# single_esc.net
KiCad netlist of a schematic drawn in Altium Designer
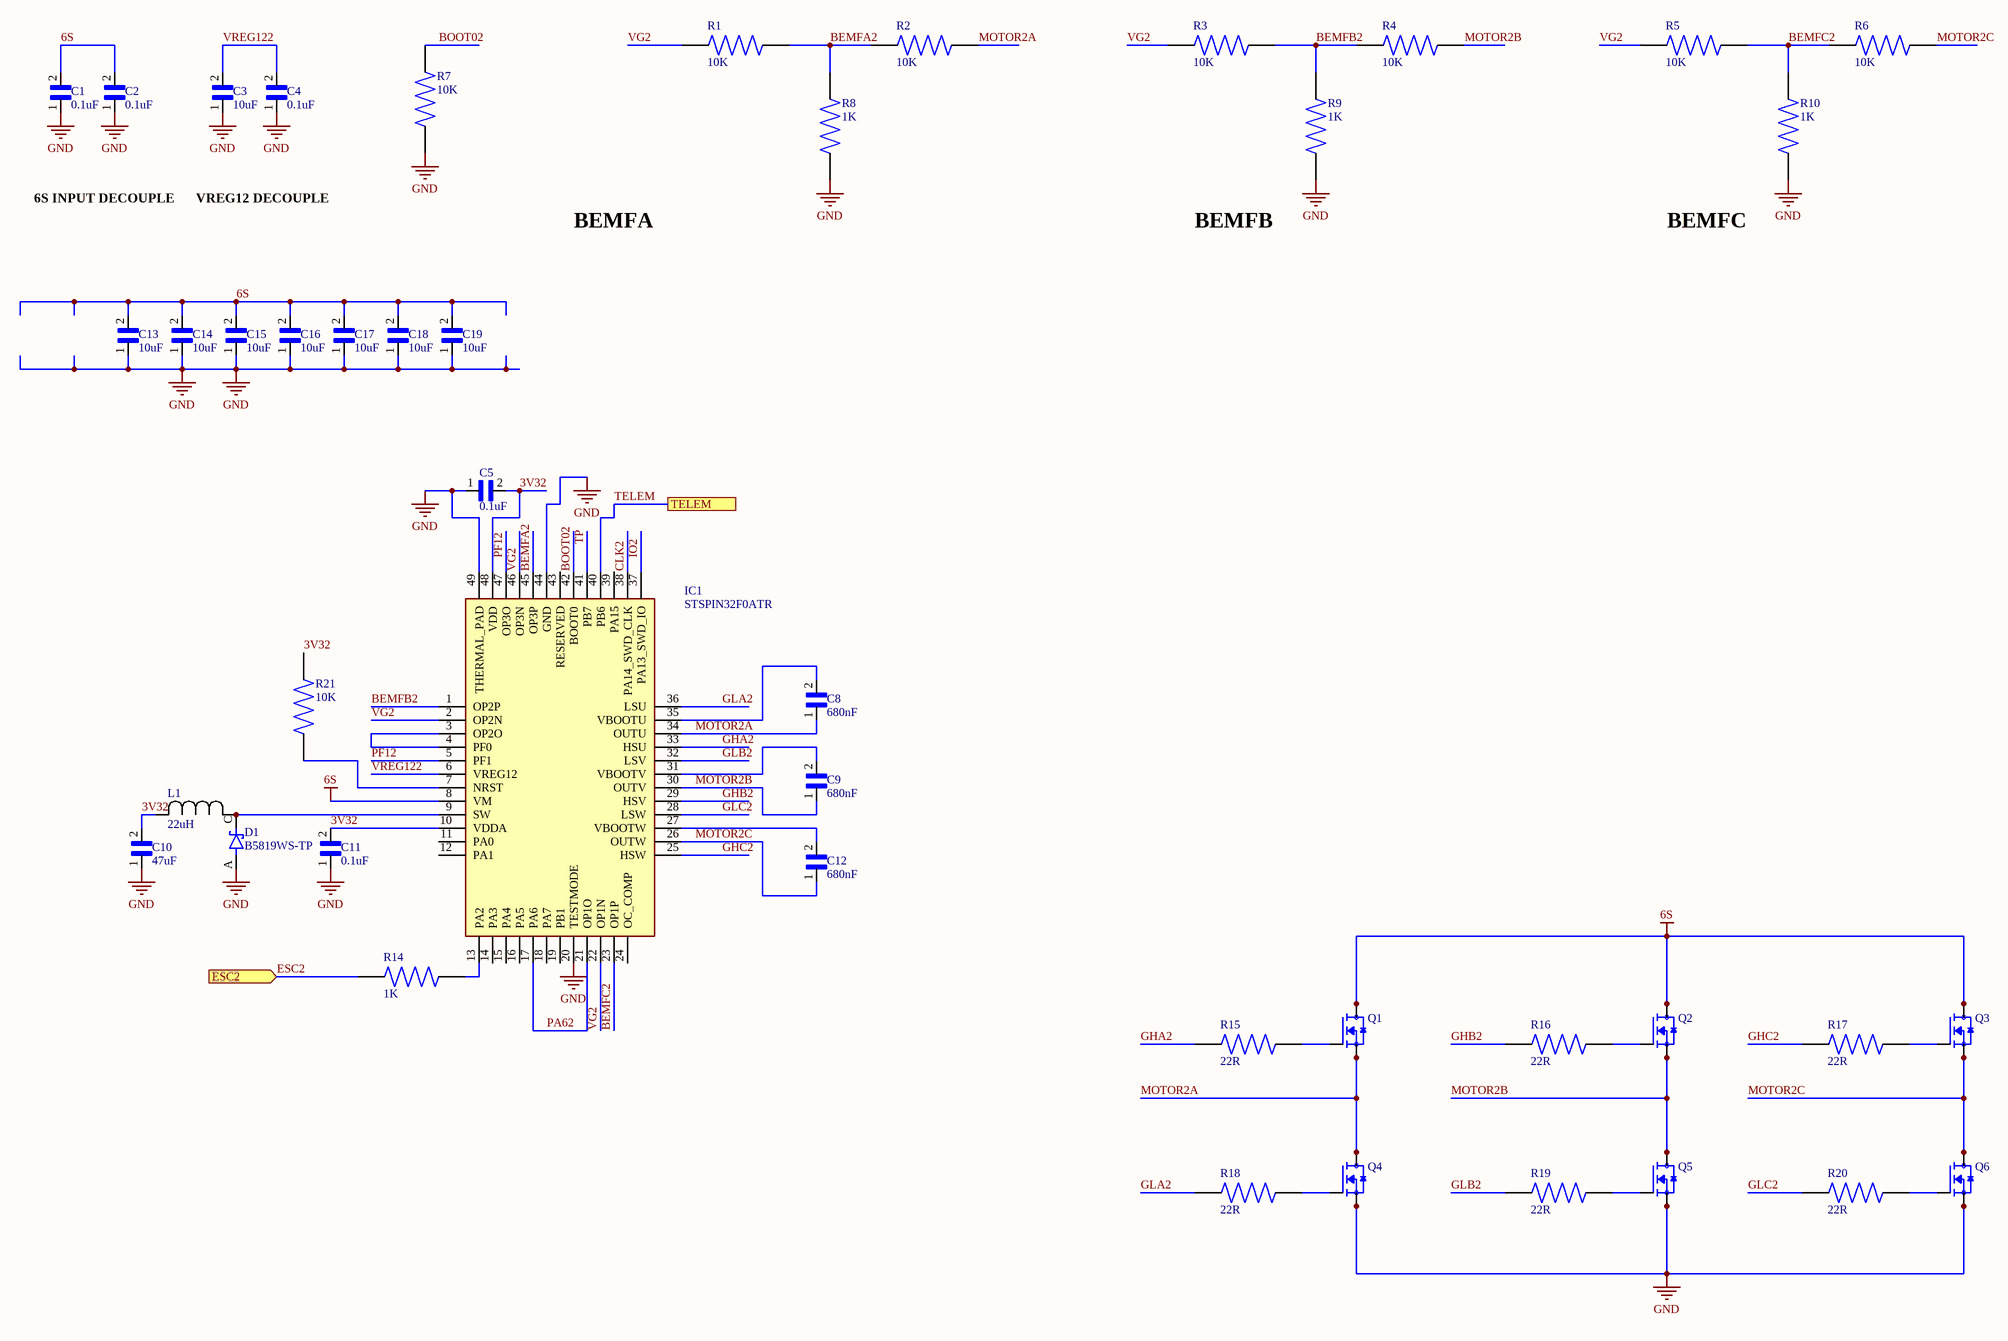
[diagram p0: single esc.SchDoc]

(export (version "E")
  (design (tool "Eeschema 10.0.6"))
  (components
    (comp (ref "C1")
      (value "0.1uF")
      (footprint "CAPC1005X55N")
      (fields (field (name "MP") "GRM1555C1H222JA01D"))
      (libsource (lib "GRM1555C1H222JA01D") (part "GRM1555C1H222JA01D"))
    )
    (comp (ref "C2")
      (value "0.1uF")
      (footprint "CAPC1005X55N")
      (fields (field (name "MP") "GRM1555C1H222JA01D"))
      (libsource (lib "GRM1555C1H222JA01D") (part "GRM1555C1H222JA01D"))
    )
    (comp (ref "C3")
      (value "10uF")
      (footprint "CAPC1608X90N")
      (description "SMD Capacitor X7R(EIA) with Capacitance: 0.22uF Tol. 5%. Rated Voltage: 25Vdc")
      (fields (field (name "MP") "GRM188R71E224JA88D"))
      (libsource (lib "GRM188R71E224JA88D") (part "GRM188R71E224JA88D"))
    )
    (comp (ref "C4")
      (value "0.1uF")
      (footprint "CAPC1005X55N")
      (fields (field (name "MP") "GRM1555C1H222JA01D"))
      (libsource (lib "GRM1555C1H222JA01D") (part "GRM1555C1H222JA01D"))
    )
    (comp (ref "C5")
      (value "0.1uF")
      (footprint "CAPC1005X55N")
      (fields (field (name "MP") "GRM1555C1H222JA01D"))
      (libsource (lib "") (part "GRM1555C1H222JA01D_1"))
    )
    (comp (ref "C8")
      (value "680nF")
      (footprint "CAPC1005X55N")
      (fields (field (name "MP") "GRM1555C1H222JA01D"))
      (libsource (lib "GRM1555C1H222JA01D") (part "GRM1555C1H222JA01D"))
    )
    (comp (ref "C9")
      (value "680nF")
      (footprint "CAPC1005X55N")
      (fields (field (name "MP") "GRM1555C1H222JA01D"))
      (libsource (lib "GRM1555C1H222JA01D") (part "GRM1555C1H222JA01D"))
    )
    (comp (ref "C10")
      (value "47uF")
      (footprint "CAPC1608X90N")
      (description "SMD Capacitor X7R(EIA) with Capacitance: 0.22uF Tol. 5%. Rated Voltage: 25Vdc")
      (fields (field (name "MP") "GRM188R71E224JA88D"))
      (libsource (lib "GRM188R71E224JA88D") (part "GRM188R71E224JA88D"))
    )
    (comp (ref "C11")
      (value "0.1uF")
      (footprint "CAPC1005X55N")
      (fields (field (name "MP") "GRM1555C1H222JA01D"))
      (libsource (lib "GRM1555C1H222JA01D") (part "GRM1555C1H222JA01D"))
    )
    (comp (ref "C12")
      (value "680nF")
      (footprint "CAPC1005X55N")
      (fields (field (name "MP") "GRM1555C1H222JA01D"))
      (libsource (lib "GRM1555C1H222JA01D") (part "GRM1555C1H222JA01D"))
    )
    (comp (ref "C13")
      (value "10uF")
      (footprint "CAPC3216X190N")
      (description "Ceramic Capacitor")
      (fields (field (name "MP") "GRM31CC80G227ME11K"))
      (libsource (lib "GRM31CC80G227ME11K") (part "GRM31CC80G227ME11K"))
    )
    (comp (ref "C14")
      (value "10uF")
      (footprint "CAPC3216X190N")
      (description "Ceramic Capacitor")
      (fields (field (name "MP") "GRM31CC80G227ME11K"))
      (libsource (lib "GRM31CC80G227ME11K") (part "GRM31CC80G227ME11K"))
    )
    (comp (ref "C15")
      (value "10uF")
      (footprint "CAPC3216X190N")
      (description "Ceramic Capacitor")
      (fields (field (name "MP") "GRM31CC80G227ME11K"))
      (libsource (lib "GRM31CC80G227ME11K") (part "GRM31CC80G227ME11K"))
    )
    (comp (ref "C16")
      (value "10uF")
      (footprint "CAPC3216X190N")
      (description "Ceramic Capacitor")
      (fields (field (name "MP") "GRM31CC80G227ME11K"))
      (libsource (lib "GRM31CC80G227ME11K") (part "GRM31CC80G227ME11K"))
    )
    (comp (ref "C17")
      (value "10uF")
      (footprint "CAPC3216X190N")
      (description "Ceramic Capacitor")
      (fields (field (name "MP") "GRM31CC80G227ME11K"))
      (libsource (lib "GRM31CC80G227ME11K") (part "GRM31CC80G227ME11K"))
    )
    (comp (ref "C18")
      (value "10uF")
      (footprint "CAPC3216X190N")
      (description "Ceramic Capacitor")
      (fields (field (name "MP") "GRM31CC80G227ME11K"))
      (libsource (lib "GRM31CC80G227ME11K") (part "GRM31CC80G227ME11K"))
    )
    (comp (ref "C19")
      (value "10uF")
      (footprint "CAPC3216X190N")
      (description "Ceramic Capacitor")
      (fields (field (name "MP") "GRM31CC80G227ME11K"))
      (libsource (lib "GRM31CC80G227ME11K") (part "GRM31CC80G227ME11K"))
    )
    (comp (ref "D1")
      (value "B5819WS-TP")
      (footprint "SOD2512X115N")
      (fields (field (name "MF") "{'manufacturer': u'Micro Commercial Components'}"))
      (libsource (lib "SnapEDA_Library") (part "B5819WS-TP"))
    )
    (comp (ref "IC1")
      (value "STSPIN32F0ATR")
      (footprint "SamacSys:QFN50P700X700X100-49N-D")
      (description "Integrated Circuit")
      (fields (field (name "MOUSER PART NUMBER") "511-STSPIN32F0ATR"))
      (libsource (lib "SamacSys") (part "STSPIN32F0ATR"))
    )
    (comp (ref "L1")
      (value "22uH")
      (footprint "IND_BOURNS_SRN3015")
      (description "No Description Available")
      (fields
        (field (name "MANUFACTURER_PART_NUMBER") "SRN3015-220M")
        (field (name "COPYRIGHT") "Copyright (C) 2022 Ultra Librarian. All rights reserved.")
      )
      (libsource (lib "SRN3015-220M") (part "SRN3015-220M"))
    )
    (comp (ref "Q1")
      (value "TPHR8504PL,L1Q")
      (footprint "TRANS_TPHR8504PL,L1Q")
      (description "N-Channel 40V 150A (Tc) 1W (Ta), 170W (Tc) Surface Mount 8-SOP Advance (5x5)")
      (fields (field (name "MF") "Toshiba Semiconductor"))
      (libsource (lib "TPHR8504PL_L1Q") (part "TPHR8504PL,L1Q"))
    )
    (comp (ref "Q2")
      (value "TPHR8504PL,L1Q")
      (footprint "TRANS_TPHR8504PL,L1Q")
      (description "N-Channel 40V 150A (Tc) 1W (Ta), 170W (Tc) Surface Mount 8-SOP Advance (5x5)")
      (fields (field (name "MF") "Toshiba Semiconductor"))
      (libsource (lib "TPHR8504PL_L1Q") (part "TPHR8504PL,L1Q"))
    )
    (comp (ref "Q3")
      (value "TPHR8504PL,L1Q")
      (footprint "TRANS_TPHR8504PL,L1Q")
      (description "N-Channel 40V 150A (Tc) 1W (Ta), 170W (Tc) Surface Mount 8-SOP Advance (5x5)")
      (fields (field (name "MF") "Toshiba Semiconductor"))
      (libsource (lib "TPHR8504PL_L1Q") (part "TPHR8504PL,L1Q"))
    )
    (comp (ref "Q4")
      (value "TPHR8504PL,L1Q")
      (footprint "TRANS_TPHR8504PL,L1Q")
      (description "N-Channel 40V 150A (Tc) 1W (Ta), 170W (Tc) Surface Mount 8-SOP Advance (5x5)")
      (fields (field (name "MF") "Toshiba Semiconductor"))
      (libsource (lib "TPHR8504PL_L1Q") (part "TPHR8504PL,L1Q"))
    )
    (comp (ref "Q5")
      (value "TPHR8504PL,L1Q")
      (footprint "TRANS_TPHR8504PL,L1Q")
      (description "N-Channel 40V 150A (Tc) 1W (Ta), 170W (Tc) Surface Mount 8-SOP Advance (5x5)")
      (fields (field (name "MF") "Toshiba Semiconductor"))
      (libsource (lib "TPHR8504PL_L1Q") (part "TPHR8504PL,L1Q"))
    )
    (comp (ref "Q6")
      (value "TPHR8504PL,L1Q")
      (footprint "TRANS_TPHR8504PL,L1Q")
      (description "N-Channel 40V 150A (Tc) 1W (Ta), 170W (Tc) Surface Mount 8-SOP Advance (5x5)")
      (fields (field (name "MF") "Toshiba Semiconductor"))
      (libsource (lib "TPHR8504PL_L1Q") (part "TPHR8504PL,L1Q"))
    )
    (comp (ref "R1")
      (value "10K")
      (footprint "RESC1005X37N")
      (fields (field (name "MP") "RE0402BRE07330KL") (field (name "MF") "{'manufacturer': u'Yageo'}"))
      (libsource (lib "SnapEDA_Library") (part "RE0402BRE07330KL"))
    )
    (comp (ref "R2")
      (value "10K")
      (footprint "RESC1005X37N")
      (fields (field (name "MP") "RE0402BRE07330KL") (field (name "MF") "{'manufacturer': u'Yageo'}"))
      (libsource (lib "SnapEDA_Library") (part "RE0402BRE07330KL"))
    )
    (comp (ref "R3")
      (value "10K")
      (footprint "RESC1005X37N")
      (fields (field (name "MP") "RE0402BRE07330KL") (field (name "MF") "{'manufacturer': u'Yageo'}"))
      (libsource (lib "SnapEDA_Library") (part "RE0402BRE07330KL"))
    )
    (comp (ref "R4")
      (value "10K")
      (footprint "RESC1005X37N")
      (fields (field (name "MP") "RE0402BRE07330KL") (field (name "MF") "{'manufacturer': u'Yageo'}"))
      (libsource (lib "SnapEDA_Library") (part "RE0402BRE07330KL"))
    )
    (comp (ref "R5")
      (value "10K")
      (footprint "RESC1005X37N")
      (fields (field (name "MP") "RE0402BRE07330KL") (field (name "MF") "{'manufacturer': u'Yageo'}"))
      (libsource (lib "SnapEDA_Library") (part "RE0402BRE07330KL"))
    )
    (comp (ref "R6")
      (value "10K")
      (footprint "RESC1005X37N")
      (fields (field (name "MP") "RE0402BRE07330KL") (field (name "MF") "{'manufacturer': u'Yageo'}"))
      (libsource (lib "SnapEDA_Library") (part "RE0402BRE07330KL"))
    )
    (comp (ref "R7")
      (value "10K")
      (footprint "RESC1005X37N")
      (fields (field (name "MP") "RE0402BRE07330KL") (field (name "MF") "{'manufacturer': u'Yageo'}"))
      (libsource (lib "SnapEDA_Library") (part "RE0402BRE07330KL"))
    )
    (comp (ref "R8")
      (value "1K")
      (footprint "RESC1005X37N")
      (fields (field (name "MP") "RE0402BRE07330KL") (field (name "MF") "{'manufacturer': u'Yageo'}"))
      (libsource (lib "SnapEDA_Library") (part "RE0402BRE07330KL"))
    )
    (comp (ref "R9")
      (value "1K")
      (footprint "RESC1005X37N")
      (fields (field (name "MP") "RE0402BRE07330KL") (field (name "MF") "{'manufacturer': u'Yageo'}"))
      (libsource (lib "SnapEDA_Library") (part "RE0402BRE07330KL"))
    )
    (comp (ref "R10")
      (value "1K")
      (footprint "RESC1005X37N")
      (fields (field (name "MP") "RE0402BRE07330KL") (field (name "MF") "{'manufacturer': u'Yageo'}"))
      (libsource (lib "SnapEDA_Library") (part "RE0402BRE07330KL"))
    )
    (comp (ref "R14")
      (value "1K")
      (footprint "RESC1005X37N")
      (fields (field (name "MP") "RE0402BRE07330KL") (field (name "MF") "{'manufacturer': u'Yageo'}"))
      (libsource (lib "SnapEDA_Library") (part "RE0402BRE07330KL"))
    )
    (comp (ref "R15")
      (value "22R")
      (footprint "RESC1005X37N")
      (fields (field (name "MP") "RE0402BRE07330KL") (field (name "MF") "{'manufacturer': u'Yageo'}"))
      (libsource (lib "SnapEDA_Library") (part "RE0402BRE07330KL"))
    )
    (comp (ref "R16")
      (value "22R")
      (footprint "RESC1005X37N")
      (fields (field (name "MP") "RE0402BRE07330KL") (field (name "MF") "{'manufacturer': u'Yageo'}"))
      (libsource (lib "SnapEDA_Library") (part "RE0402BRE07330KL"))
    )
    (comp (ref "R17")
      (value "22R")
      (footprint "RESC1005X37N")
      (fields (field (name "MP") "RE0402BRE07330KL") (field (name "MF") "{'manufacturer': u'Yageo'}"))
      (libsource (lib "SnapEDA_Library") (part "RE0402BRE07330KL"))
    )
    (comp (ref "R18")
      (value "22R")
      (footprint "RESC1005X37N")
      (fields (field (name "MP") "RE0402BRE07330KL") (field (name "MF") "{'manufacturer': u'Yageo'}"))
      (libsource (lib "SnapEDA_Library") (part "RE0402BRE07330KL"))
    )
    (comp (ref "R19")
      (value "22R")
      (footprint "RESC1005X37N")
      (fields (field (name "MP") "RE0402BRE07330KL") (field (name "MF") "{'manufacturer': u'Yageo'}"))
      (libsource (lib "SnapEDA_Library") (part "RE0402BRE07330KL"))
    )
    (comp (ref "R20")
      (value "22R")
      (footprint "RESC1005X37N")
      (fields (field (name "MP") "RE0402BRE07330KL") (field (name "MF") "{'manufacturer': u'Yageo'}"))
      (libsource (lib "SnapEDA_Library") (part "RE0402BRE07330KL"))
    )
    (comp (ref "R21")
      (value "10K")
      (footprint "RESC1005X37N")
      (fields (field (name "MP") "RE0402BRE07330KL") (field (name "MF") "{'manufacturer': u'Yageo'}"))
      (libsource (lib "SnapEDA_Library") (part "RE0402BRE07330KL"))
    )
  )
  (nets
    (net (code "1") (name "/3V32") (class "Default")
      (node (ref "C10") (pin "2") (pinfunction "2_2") (pintype "passive"))
      (node (ref "C11") (pin "2") (pinfunction "2_2") (pintype "passive"))
      (node (ref "C5") (pin "2") (pinfunction "2_2") (pintype "passive"))
      (node (ref "IC1") (pin "10") (pinfunction "VDDA_10") (pintype "passive"))
      (node (ref "IC1") (pin "48") (pinfunction "VDD_48") (pintype "passive"))
      (node (ref "L1") (pin "2") (pinfunction "2_2") (pintype "passive"))
      (node (ref "R21") (pin "2") (pinfunction "2_2") (pintype "passive"))
    )
    (net (code "2") (name "/BEMFA2") (class "Default")
      (node (ref "IC1") (pin "45") (pinfunction "OP3P_45") (pintype "passive"))
      (node (ref "R1") (pin "1") (pinfunction "1_1") (pintype "passive"))
      (node (ref "R2") (pin "2") (pinfunction "2_2") (pintype "passive"))
      (node (ref "R8") (pin "1") (pinfunction "1_1") (pintype "passive"))
    )
    (net (code "3") (name "/BEMFB2") (class "Default")
      (node (ref "IC1") (pin "1") (pinfunction "OP2P_1") (pintype "passive"))
      (node (ref "R3") (pin "1") (pinfunction "1_1") (pintype "passive"))
      (node (ref "R4") (pin "2") (pinfunction "2_2") (pintype "passive"))
      (node (ref "R9") (pin "1") (pinfunction "1_1") (pintype "passive"))
    )
    (net (code "4") (name "/BEMFC2") (class "Default")
      (node (ref "IC1") (pin "23") (pinfunction "OP1P_23") (pintype "passive"))
      (node (ref "R10") (pin "1") (pinfunction "1_1") (pintype "passive"))
      (node (ref "R5") (pin "1") (pinfunction "1_1") (pintype "passive"))
      (node (ref "R6") (pin "2") (pinfunction "2_2") (pintype "passive"))
    )
    (net (code "5") (name "/BOOT02") (class "Default")
      (node (ref "IC1") (pin "42") (pinfunction "BOOT0_42") (pintype "passive"))
      (node (ref "R7") (pin "2") (pinfunction "2_2") (pintype "passive"))
    )
    (net (code "6") (name "/CLK2") (class "Default")
      (node (ref "IC1") (pin "38") (pinfunction "PA14_SWD_CLK_38") (pintype "passive"))
    )
    (net (code "7") (name "/ESC2") (class "Default")
      (node (ref "R14") (pin "1") (pinfunction "1_1") (pintype "passive"))
    )
    (net (code "8") (name "/GHA2") (class "Default")
      (node (ref "IC1") (pin "33") (pinfunction "HSU_33") (pintype "passive"))
      (node (ref "R15") (pin "2") (pinfunction "2_2") (pintype "passive"))
    )
    (net (code "9") (name "/GHB2") (class "Default")
      (node (ref "IC1") (pin "29") (pinfunction "HSV_29") (pintype "passive"))
      (node (ref "R16") (pin "2") (pinfunction "2_2") (pintype "passive"))
    )
    (net (code "10") (name "/GHC2") (class "Default")
      (node (ref "IC1") (pin "25") (pinfunction "HSW_25") (pintype "passive"))
      (node (ref "R17") (pin "2") (pinfunction "2_2") (pintype "passive"))
    )
    (net (code "11") (name "/GLA2") (class "Default")
      (node (ref "IC1") (pin "36") (pinfunction "LSU_36") (pintype "passive"))
      (node (ref "R18") (pin "2") (pinfunction "2_2") (pintype "passive"))
    )
    (net (code "12") (name "/GLB2") (class "Default")
      (node (ref "IC1") (pin "32") (pinfunction "LSV_32") (pintype "passive"))
      (node (ref "R19") (pin "2") (pinfunction "2_2") (pintype "passive"))
    )
    (net (code "13") (name "/GLC2") (class "Default")
      (node (ref "IC1") (pin "28") (pinfunction "LSW_28") (pintype "passive"))
      (node (ref "R20") (pin "2") (pinfunction "2_2") (pintype "passive"))
    )
    (net (code "14") (name "/IO2") (class "Default")
      (node (ref "IC1") (pin "37") (pinfunction "PA13_SWD_IO_37") (pintype "passive"))
    )
    (net (code "15") (name "/MOTOR2A") (class "Default")
      (node (ref "C8") (pin "1") (pinfunction "1_1") (pintype "passive"))
      (node (ref "IC1") (pin "34") (pinfunction "OUTU_34") (pintype "passive"))
      (node (ref "Q1") (pin "1") (pinfunction "S_1") (pintype "passive"))
      (node (ref "Q1") (pin "2") (pinfunction "S_2") (pintype "passive"))
      (node (ref "Q1") (pin "3") (pinfunction "S_3") (pintype "passive"))
      (node (ref "Q4") (pin "5") (pinfunction "D_5") (pintype "passive"))
      (node (ref "Q4") (pin "6") (pinfunction "D_6") (pintype "passive"))
      (node (ref "Q4") (pin "7") (pinfunction "D_7") (pintype "passive"))
      (node (ref "Q4") (pin "8") (pinfunction "D_8") (pintype "passive"))
      (node (ref "Q4") (pin "9") (pinfunction "D_9") (pintype "passive"))
      (node (ref "R2") (pin "1") (pinfunction "1_1") (pintype "passive"))
    )
    (net (code "16") (name "/MOTOR2B") (class "Default")
      (node (ref "C9") (pin "1") (pinfunction "1_1") (pintype "passive"))
      (node (ref "IC1") (pin "30") (pinfunction "OUTV_30") (pintype "passive"))
      (node (ref "Q2") (pin "1") (pinfunction "S_1") (pintype "passive"))
      (node (ref "Q2") (pin "2") (pinfunction "S_2") (pintype "passive"))
      (node (ref "Q2") (pin "3") (pinfunction "S_3") (pintype "passive"))
      (node (ref "Q5") (pin "5") (pinfunction "D_5") (pintype "passive"))
      (node (ref "Q5") (pin "6") (pinfunction "D_6") (pintype "passive"))
      (node (ref "Q5") (pin "7") (pinfunction "D_7") (pintype "passive"))
      (node (ref "Q5") (pin "8") (pinfunction "D_8") (pintype "passive"))
      (node (ref "Q5") (pin "9") (pinfunction "D_9") (pintype "passive"))
      (node (ref "R4") (pin "1") (pinfunction "1_1") (pintype "passive"))
    )
    (net (code "17") (name "/MOTOR2C") (class "Default")
      (node (ref "C12") (pin "1") (pinfunction "1_1") (pintype "passive"))
      (node (ref "IC1") (pin "26") (pinfunction "OUTW_26") (pintype "passive"))
      (node (ref "Q3") (pin "1") (pinfunction "S_1") (pintype "passive"))
      (node (ref "Q3") (pin "2") (pinfunction "S_2") (pintype "passive"))
      (node (ref "Q3") (pin "3") (pinfunction "S_3") (pintype "passive"))
      (node (ref "Q6") (pin "5") (pinfunction "D_5") (pintype "passive"))
      (node (ref "Q6") (pin "6") (pinfunction "D_6") (pintype "passive"))
      (node (ref "Q6") (pin "7") (pinfunction "D_7") (pintype "passive"))
      (node (ref "Q6") (pin "8") (pinfunction "D_8") (pintype "passive"))
      (node (ref "Q6") (pin "9") (pinfunction "D_9") (pintype "passive"))
      (node (ref "R6") (pin "1") (pinfunction "1_1") (pintype "passive"))
    )
    (net (code "18") (name "/PA62") (class "Default")
      (node (ref "IC1") (pin "17") (pinfunction "PA6_17") (pintype "passive"))
      (node (ref "IC1") (pin "21") (pinfunction "OP1O_21") (pintype "passive"))
    )
    (net (code "19") (name "/PF12") (class "Default")
      (node (ref "IC1") (pin "47") (pinfunction "OP3O_47") (pintype "passive"))
      (node (ref "IC1") (pin "5") (pinfunction "PF1_5") (pintype "passive"))
    )
    (net (code "20") (name "/TELEM") (class "Default")
      (node (ref "IC1") (pin "40") (pinfunction "PB6_40") (pintype "passive"))
    )
    (net (code "21") (name "/TP") (class "Default")
      (node (ref "IC1") (pin "41") (pinfunction "PB7_41") (pintype "passive"))
    )
    (net (code "22") (name "/VG2") (class "Default")
      (node (ref "IC1") (pin "2") (pinfunction "OP2N_2") (pintype "passive"))
      (node (ref "IC1") (pin "22") (pinfunction "OP1N_22") (pintype "passive"))
      (node (ref "IC1") (pin "46") (pinfunction "OP3N_46") (pintype "passive"))
      (node (ref "R1") (pin "2") (pinfunction "2_2") (pintype "passive"))
      (node (ref "R3") (pin "2") (pinfunction "2_2") (pintype "passive"))
      (node (ref "R5") (pin "2") (pinfunction "2_2") (pintype "passive"))
    )
    (net (code "23") (name "/VREG122") (class "Default")
      (node (ref "C3") (pin "2") (pinfunction "2_2") (pintype "passive"))
      (node (ref "C4") (pin "2") (pinfunction "2_2") (pintype "passive"))
      (node (ref "IC1") (pin "6") (pinfunction "VREG12_6") (pintype "passive"))
    )
    (net (code "24") (name "6S") (class "Default")
      (node (ref "C1") (pin "2") (pinfunction "2_2") (pintype "passive"))
      (node (ref "C13") (pin "2") (pinfunction "2_2") (pintype "passive"))
      (node (ref "C14") (pin "2") (pinfunction "2_2") (pintype "passive"))
      (node (ref "C15") (pin "2") (pinfunction "2_2") (pintype "passive"))
      (node (ref "C16") (pin "2") (pinfunction "2_2") (pintype "passive"))
      (node (ref "C17") (pin "2") (pinfunction "2_2") (pintype "passive"))
      (node (ref "C18") (pin "2") (pinfunction "2_2") (pintype "passive"))
      (node (ref "C19") (pin "2") (pinfunction "2_2") (pintype "passive"))
      (node (ref "C2") (pin "2") (pinfunction "2_2") (pintype "passive"))
      (node (ref "IC1") (pin "8") (pinfunction "VM_8") (pintype "passive"))
      (node (ref "Q1") (pin "5") (pinfunction "D_5") (pintype "passive"))
      (node (ref "Q1") (pin "6") (pinfunction "D_6") (pintype "passive"))
      (node (ref "Q1") (pin "7") (pinfunction "D_7") (pintype "passive"))
      (node (ref "Q1") (pin "8") (pinfunction "D_8") (pintype "passive"))
      (node (ref "Q1") (pin "9") (pinfunction "D_9") (pintype "passive"))
      (node (ref "Q2") (pin "5") (pinfunction "D_5") (pintype "passive"))
      (node (ref "Q2") (pin "6") (pinfunction "D_6") (pintype "passive"))
      (node (ref "Q2") (pin "7") (pinfunction "D_7") (pintype "passive"))
      (node (ref "Q2") (pin "8") (pinfunction "D_8") (pintype "passive"))
      (node (ref "Q2") (pin "9") (pinfunction "D_9") (pintype "passive"))
      (node (ref "Q3") (pin "5") (pinfunction "D_5") (pintype "passive"))
      (node (ref "Q3") (pin "6") (pinfunction "D_6") (pintype "passive"))
      (node (ref "Q3") (pin "7") (pinfunction "D_7") (pintype "passive"))
      (node (ref "Q3") (pin "8") (pinfunction "D_8") (pintype "passive"))
      (node (ref "Q3") (pin "9") (pinfunction "D_9") (pintype "passive"))
    )
    (net (code "25") (name "GND") (class "Default")
      (node (ref "C1") (pin "1") (pinfunction "1_1") (pintype "passive"))
      (node (ref "C10") (pin "1") (pinfunction "1_1") (pintype "passive"))
      (node (ref "C11") (pin "1") (pinfunction "1_1") (pintype "passive"))
      (node (ref "C13") (pin "1") (pinfunction "1_1") (pintype "passive"))
      (node (ref "C14") (pin "1") (pinfunction "1_1") (pintype "passive"))
      (node (ref "C15") (pin "1") (pinfunction "1_1") (pintype "passive"))
      (node (ref "C16") (pin "1") (pinfunction "1_1") (pintype "passive"))
      (node (ref "C17") (pin "1") (pinfunction "1_1") (pintype "passive"))
      (node (ref "C18") (pin "1") (pinfunction "1_1") (pintype "passive"))
      (node (ref "C19") (pin "1") (pinfunction "1_1") (pintype "passive"))
      (node (ref "C2") (pin "1") (pinfunction "1_1") (pintype "passive"))
      (node (ref "C3") (pin "1") (pinfunction "1_1") (pintype "passive"))
      (node (ref "C4") (pin "1") (pinfunction "1_1") (pintype "passive"))
      (node (ref "C5") (pin "1") (pinfunction "1_1") (pintype "passive"))
      (node (ref "D1") (pin "A") (pinfunction "A_A") (pintype "passive"))
      (node (ref "IC1") (pin "20") (pinfunction "TESTMODE_20") (pintype "passive"))
      (node (ref "IC1") (pin "44") (pinfunction "GND_44") (pintype "passive"))
      (node (ref "IC1") (pin "49") (pinfunction "THERMAL_PAD_49") (pintype "passive"))
      (node (ref "Q4") (pin "1") (pinfunction "S_1") (pintype "passive"))
      (node (ref "Q4") (pin "2") (pinfunction "S_2") (pintype "passive"))
      (node (ref "Q4") (pin "3") (pinfunction "S_3") (pintype "passive"))
      (node (ref "Q5") (pin "1") (pinfunction "S_1") (pintype "passive"))
      (node (ref "Q5") (pin "2") (pinfunction "S_2") (pintype "passive"))
      (node (ref "Q5") (pin "3") (pinfunction "S_3") (pintype "passive"))
      (node (ref "Q6") (pin "1") (pinfunction "S_1") (pintype "passive"))
      (node (ref "Q6") (pin "2") (pinfunction "S_2") (pintype "passive"))
      (node (ref "Q6") (pin "3") (pinfunction "S_3") (pintype "passive"))
      (node (ref "R10") (pin "2") (pinfunction "2_2") (pintype "passive"))
      (node (ref "R7") (pin "1") (pinfunction "1_1") (pintype "passive"))
      (node (ref "R8") (pin "2") (pinfunction "2_2") (pintype "passive"))
      (node (ref "R9") (pin "2") (pinfunction "2_2") (pintype "passive"))
    )
    (net (code "26") (name "Net-(D1-K)") (class "Default")
      (node (ref "D1") (pin "C") (pinfunction "K_C") (pintype "passive"))
      (node (ref "IC1") (pin "9") (pinfunction "SW_9") (pintype "passive"))
      (node (ref "L1") (pin "1") (pinfunction "1_1") (pintype "passive"))
    )
    (net (code "27") (name "Net-(IC1-NRST)") (class "Default")
      (node (ref "IC1") (pin "7") (pinfunction "NRST_7") (pintype "passive"))
      (node (ref "R21") (pin "1") (pinfunction "1_1") (pintype "passive"))
    )
    (net (code "28") (name "Net-(IC1-OP2O)") (class "Default")
      (node (ref "IC1") (pin "3") (pinfunction "OP2O_3") (pintype "passive"))
      (node (ref "IC1") (pin "4") (pinfunction "PF0_4") (pintype "passive"))
    )
    (net (code "29") (name "Net-(IC1-PA2)") (class "Default")
      (node (ref "IC1") (pin "13") (pinfunction "PA2_13") (pintype "passive"))
      (node (ref "R14") (pin "2") (pinfunction "2_2") (pintype "passive"))
    )
    (net (code "30") (name "Net-(IC1-VBOOTU)") (class "Default")
      (node (ref "C8") (pin "2") (pinfunction "2_2") (pintype "passive"))
      (node (ref "IC1") (pin "35") (pinfunction "VBOOTU_35") (pintype "passive"))
    )
    (net (code "31") (name "Net-(IC1-VBOOTV)") (class "Default")
      (node (ref "C9") (pin "2") (pinfunction "2_2") (pintype "passive"))
      (node (ref "IC1") (pin "31") (pinfunction "VBOOTV_31") (pintype "passive"))
    )
    (net (code "32") (name "Net-(IC1-VBOOTW)") (class "Default")
      (node (ref "C12") (pin "2") (pinfunction "2_2") (pintype "passive"))
      (node (ref "IC1") (pin "27") (pinfunction "VBOOTW_27") (pintype "passive"))
    )
    (net (code "33") (name "Net-(Q1-G)") (class "Default")
      (node (ref "Q1") (pin "4") (pinfunction "G_4") (pintype "passive"))
      (node (ref "R15") (pin "1") (pinfunction "1_1") (pintype "passive"))
    )
    (net (code "34") (name "Net-(Q2-G)") (class "Default")
      (node (ref "Q2") (pin "4") (pinfunction "G_4") (pintype "passive"))
      (node (ref "R16") (pin "1") (pinfunction "1_1") (pintype "passive"))
    )
    (net (code "35") (name "Net-(Q3-G)") (class "Default")
      (node (ref "Q3") (pin "4") (pinfunction "G_4") (pintype "passive"))
      (node (ref "R17") (pin "1") (pinfunction "1_1") (pintype "passive"))
    )
    (net (code "36") (name "Net-(Q4-G)") (class "Default")
      (node (ref "Q4") (pin "4") (pinfunction "G_4") (pintype "passive"))
      (node (ref "R18") (pin "1") (pinfunction "1_1") (pintype "passive"))
    )
    (net (code "37") (name "Net-(Q5-G)") (class "Default")
      (node (ref "Q5") (pin "4") (pinfunction "G_4") (pintype "passive"))
      (node (ref "R19") (pin "1") (pinfunction "1_1") (pintype "passive"))
    )
    (net (code "38") (name "Net-(Q6-G)") (class "Default")
      (node (ref "Q6") (pin "4") (pinfunction "G_4") (pintype "passive"))
      (node (ref "R20") (pin "1") (pinfunction "1_1") (pintype "passive"))
    )
    (net (code "39") (name "unconnected-(IC1-OC_COMP-Pad24)") (class "Default")
      (node (ref "IC1") (pin "24") (pinfunction "OC_COMP_24") (pintype "passive"))
    )
    (net (code "40") (name "unconnected-(IC1-PA0-Pad11)") (class "Default")
      (node (ref "IC1") (pin "11") (pinfunction "PA0_11") (pintype "passive"))
    )
    (net (code "41") (name "unconnected-(IC1-PA1-Pad12)") (class "Default")
      (node (ref "IC1") (pin "12") (pinfunction "PA1_12") (pintype "passive"))
    )
    (net (code "42") (name "unconnected-(IC1-PA3-Pad14)") (class "Default")
      (node (ref "IC1") (pin "14") (pinfunction "PA3_14") (pintype "passive"))
    )
    (net (code "43") (name "unconnected-(IC1-PA4-Pad15)") (class "Default")
      (node (ref "IC1") (pin "15") (pinfunction "PA4_15") (pintype "passive"))
    )
    (net (code "44") (name "unconnected-(IC1-PA5-Pad16)") (class "Default")
      (node (ref "IC1") (pin "16") (pinfunction "PA5_16") (pintype "passive"))
    )
    (net (code "45") (name "unconnected-(IC1-PA7-Pad18)") (class "Default")
      (node (ref "IC1") (pin "18") (pinfunction "PA7_18") (pintype "passive"))
    )
    (net (code "46") (name "unconnected-(IC1-PA15-Pad39)") (class "Default")
      (node (ref "IC1") (pin "39") (pinfunction "PA15_39") (pintype "passive"))
    )
    (net (code "47") (name "unconnected-(IC1-PB1-Pad19)") (class "Default")
      (node (ref "IC1") (pin "19") (pinfunction "PB1_19") (pintype "passive"))
    )
    (net (code "48") (name "unconnected-(IC1-RESERVED-Pad43)") (class "Default")
      (node (ref "IC1") (pin "43") (pinfunction "RESERVED_43") (pintype "passive"))
    )
  )
)
